# SCH_Aether_Zero_R0_1.net
KiCad netlist of a schematic drawn in EasyEDA
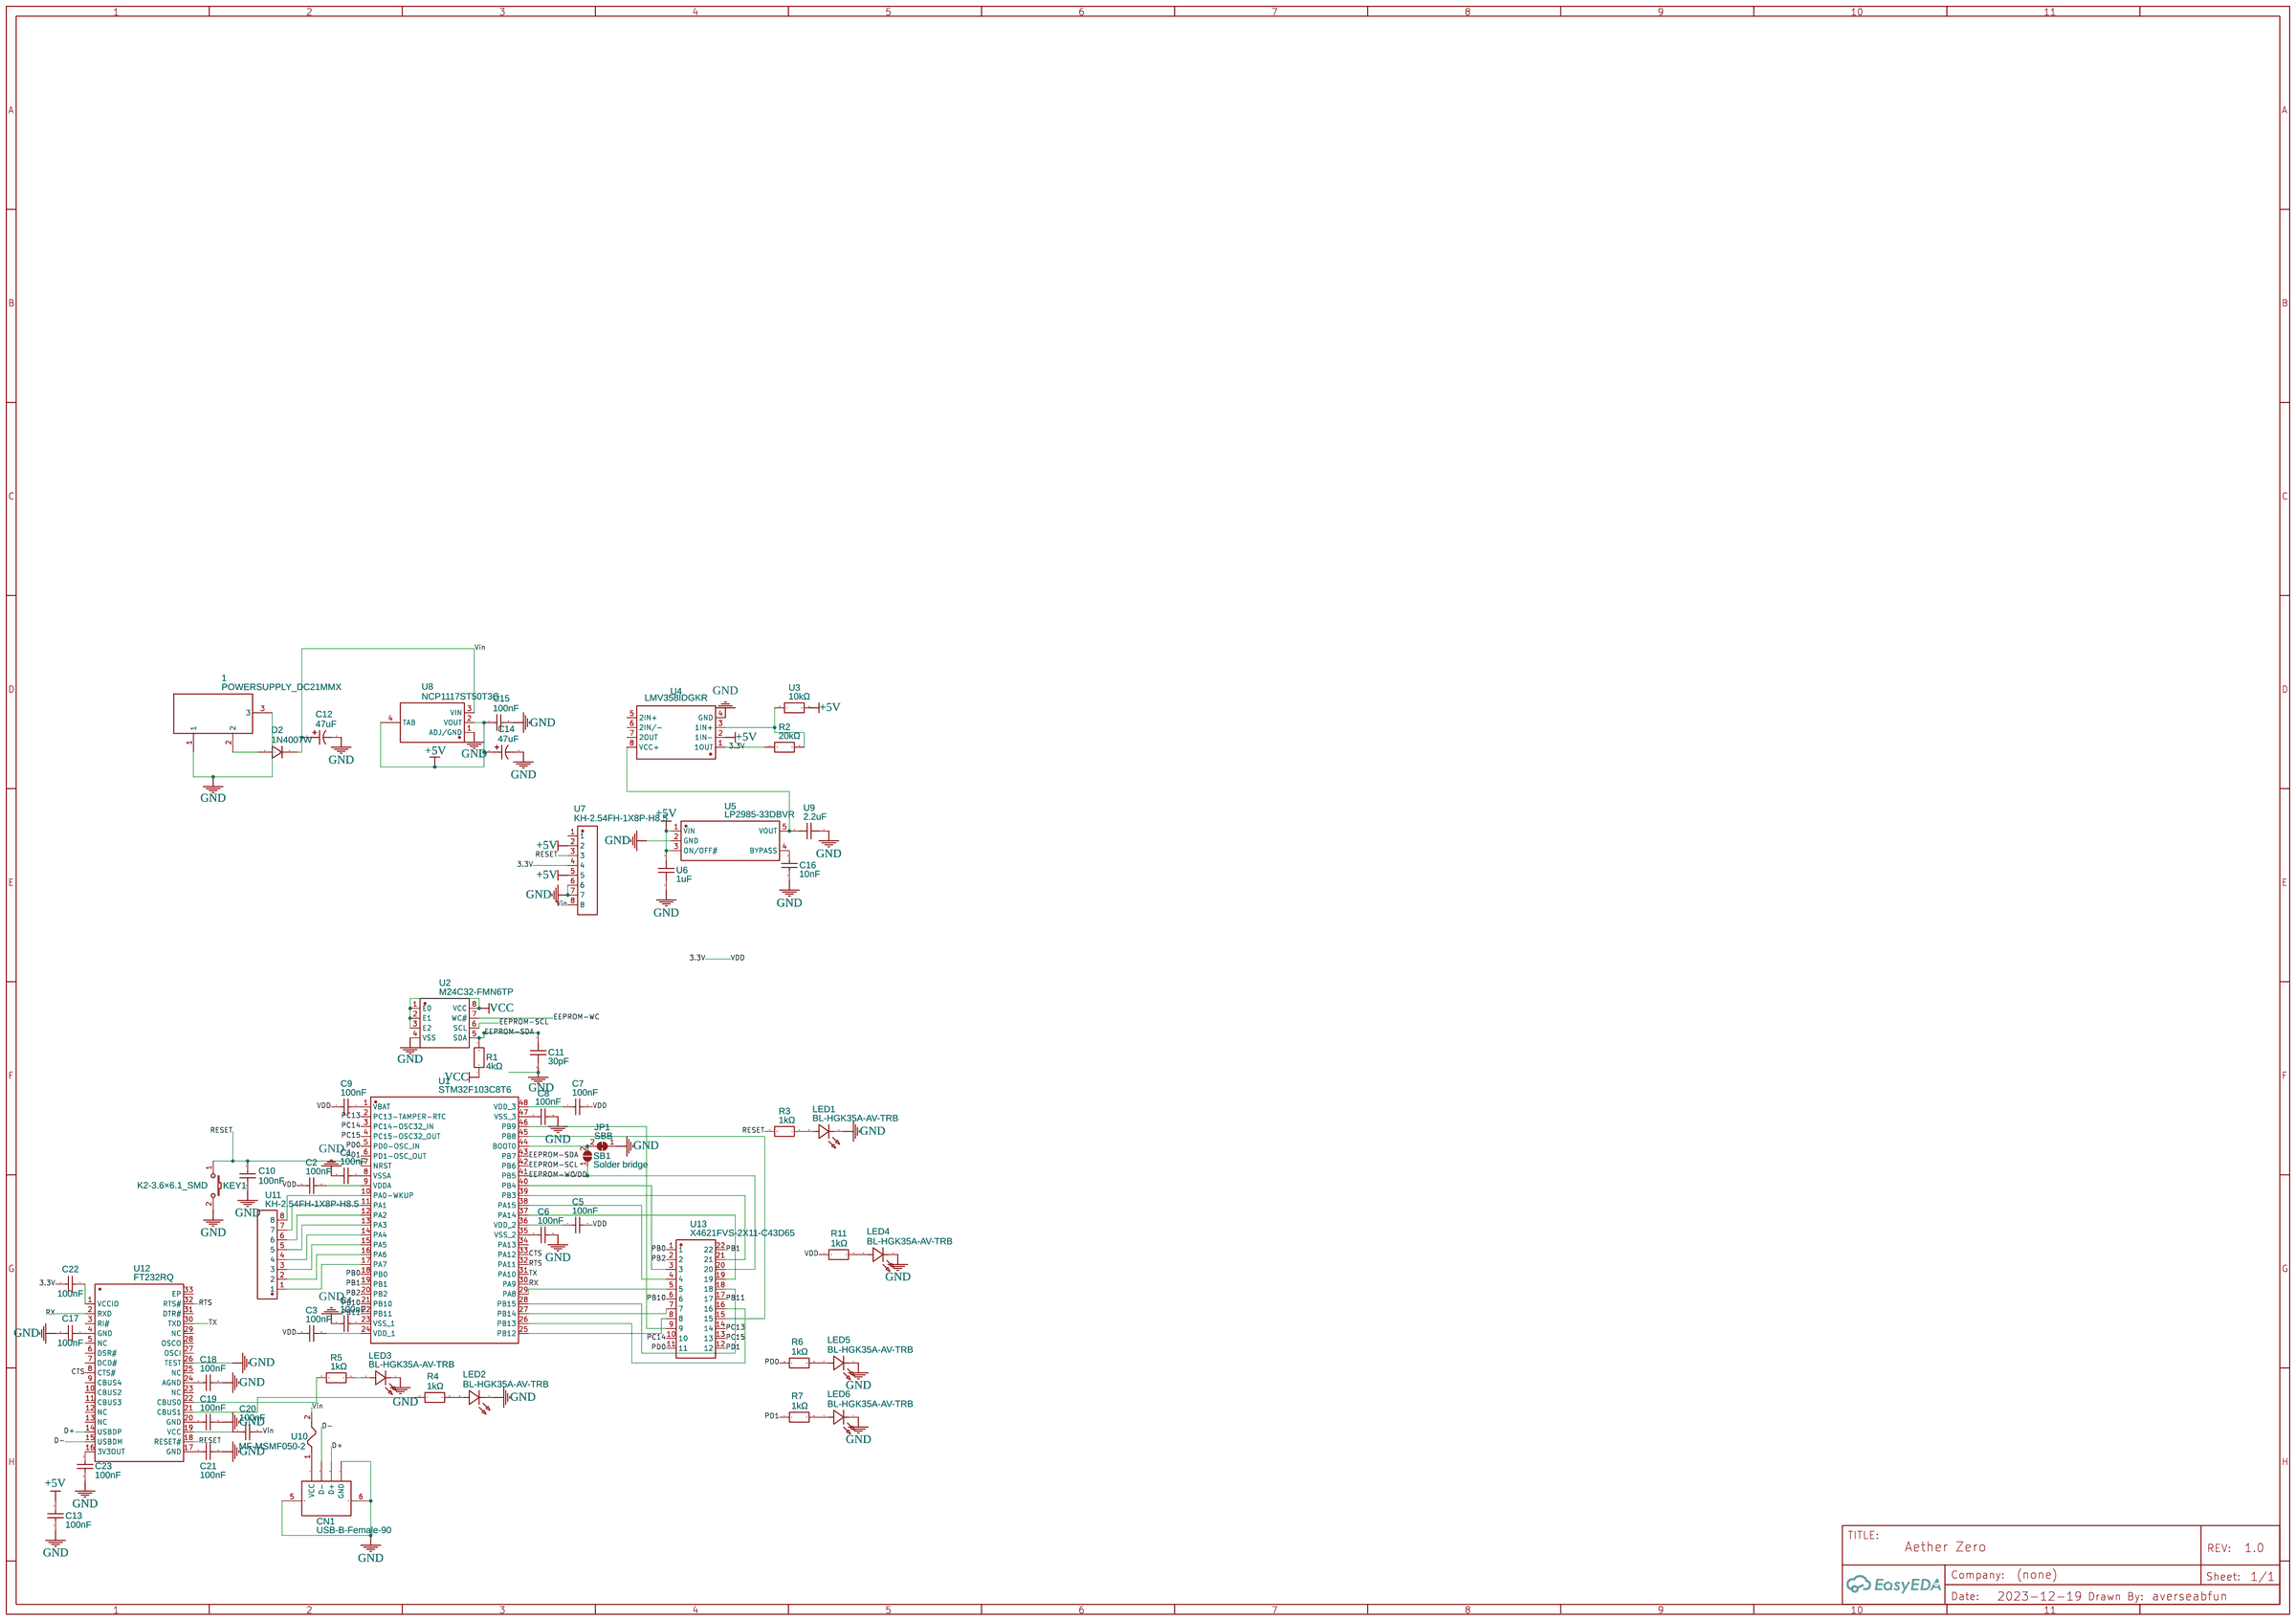
[diagram p0: schematic sheet]

(export (version "E")
  (design (tool "Eeschema 10.0.6"))
  (components
    (comp (ref "1") (value "POWERSUPPLY_DC21MMX") (libsource (lib "") (part "POWERSUPPLY_DC21MMX")))
    (comp (ref "C1")
      (value "100nF")
      (fields (field (name "Manufacturer Part") "0402B104K160NT") (field (name "Manufacturer") "FH(风华)"))
      (libsource (lib "") (part "0402B104K160NT_2"))
    )
    (comp (ref "C2")
      (value "100nF")
      (fields (field (name "Manufacturer Part") "0402B104K160NT") (field (name "Manufacturer") "FH(风华)"))
      (libsource (lib "") (part "0402B104K160NT_2"))
    )
    (comp (ref "C3")
      (value "100nF")
      (fields (field (name "Manufacturer Part") "0402B104K160NT") (field (name "Manufacturer") "FH(风华)"))
      (libsource (lib "") (part "0402B104K160NT_2"))
    )
    (comp (ref "C4")
      (value "100nF")
      (fields (field (name "Manufacturer Part") "0402B104K160NT") (field (name "Manufacturer") "FH(风华)"))
      (libsource (lib "") (part "0402B104K160NT_2"))
    )
    (comp (ref "C5")
      (value "100nF")
      (fields (field (name "Manufacturer Part") "0402B104K160NT") (field (name "Manufacturer") "FH(风华)"))
      (libsource (lib "") (part "0402B104K160NT"))
    )
    (comp (ref "C6")
      (value "100nF")
      (fields (field (name "Manufacturer Part") "0402B104K160NT") (field (name "Manufacturer") "FH(风华)"))
      (libsource (lib "") (part "0402B104K160NT"))
    )
    (comp (ref "C7")
      (value "100nF")
      (fields (field (name "Manufacturer Part") "0402B104K160NT") (field (name "Manufacturer") "FH(风华)"))
      (libsource (lib "") (part "0402B104K160NT"))
    )
    (comp (ref "C8")
      (value "100nF")
      (fields (field (name "Manufacturer Part") "0402B104K160NT") (field (name "Manufacturer") "FH(风华)"))
      (libsource (lib "") (part "0402B104K160NT"))
    )
    (comp (ref "C9")
      (value "100nF")
      (fields (field (name "Manufacturer Part") "0402B104K160NT") (field (name "Manufacturer") "FH(风华)"))
      (libsource (lib "") (part "0402B104K160NT_2"))
    )
    (comp (ref "C10")
      (value "100nF")
      (fields (field (name "Manufacturer Part") "0402B104K160NT") (field (name "Manufacturer") "FH(风华)"))
      (libsource (lib "") (part "0402B104K160NT_1"))
    )
    (comp (ref "C11")
      (value "30pF")
      (fields
        (field (name "Manufacturer Part") "AC0402JRNPO9BN300")
        (field (name "Manufacturer") "YAGEO(国巨)")
      )
      (libsource (lib "") (part "AC0402JRNPO9BN300"))
    )
    (comp (ref "C12")
      (value "47uF")
      (fields
        (field (name "Manufacturer Part") "RVT47UF35V67RV0039")
        (field (name "Manufacturer") "KNSCHA(科尼盛)")
      )
      (libsource (lib "") (part "RVT47UF35V67RV0039"))
    )
    (comp (ref "C13")
      (value "100nF")
      (fields (field (name "Manufacturer Part") "0402B104K160NT") (field (name "Manufacturer") "FH(风华)"))
      (libsource (lib "") (part "0402B104K160NT_3"))
    )
    (comp (ref "C14")
      (value "47uF")
      (fields
        (field (name "Manufacturer Part") "RVT47UF35V67RV0039")
        (field (name "Manufacturer") "KNSCHA(科尼盛)")
      )
      (libsource (lib "") (part "RVT47UF35V67RV0039"))
    )
    (comp (ref "C15")
      (value "100nF")
      (fields (field (name "Manufacturer Part") "0402B104K160NT") (field (name "Manufacturer") "FH(风华)"))
      (libsource (lib "") (part "0402B104K160NT"))
    )
    (comp (ref "C16")
      (value "10nF")
      (fields (field (name "Manufacturer Part") "0402B103K500NT") (field (name "Manufacturer") "FH(风华)"))
      (libsource (lib "") (part "0402B103K500NT"))
    )
    (comp (ref "C17")
      (value "100nF")
      (fields (field (name "Manufacturer Part") "0402B104K160NT") (field (name "Manufacturer") "FH(风华)"))
      (libsource (lib "") (part "0402B104K160NT_2"))
    )
    (comp (ref "C18")
      (value "100nF")
      (fields (field (name "Manufacturer Part") "0402B104K160NT") (field (name "Manufacturer") "FH(风华)"))
      (libsource (lib "") (part "0402B104K160NT"))
    )
    (comp (ref "C19")
      (value "100nF")
      (fields (field (name "Manufacturer Part") "0402B104K160NT") (field (name "Manufacturer") "FH(风华)"))
      (libsource (lib "") (part "0402B104K160NT"))
    )
    (comp (ref "C20")
      (value "100nF")
      (fields (field (name "Manufacturer Part") "0402B104K160NT") (field (name "Manufacturer") "FH(风华)"))
      (libsource (lib "") (part "0402B104K160NT"))
    )
    (comp (ref "C21")
      (value "100nF")
      (fields (field (name "Manufacturer Part") "0402B104K160NT") (field (name "Manufacturer") "FH(风华)"))
      (libsource (lib "") (part "0402B104K160NT"))
    )
    (comp (ref "C22")
      (value "100nF")
      (fields (field (name "Manufacturer Part") "0402B104K160NT") (field (name "Manufacturer") "FH(风华)"))
      (libsource (lib "") (part "0402B104K160NT_2"))
    )
    (comp (ref "C23")
      (value "100nF")
      (fields (field (name "Manufacturer Part") "0402B104K160NT") (field (name "Manufacturer") "FH(风华)"))
      (libsource (lib "") (part "0402B104K160NT_1"))
    )
    (comp (ref "CN1")
      (value "USB-B-Female-90")
      (fields (field (name "Manufacturer Part") "921-111A1010D10200") (field (name "Manufacturer") "精拓金"))
      (libsource (lib "") (part "USB-B-Female-90"))
    )
    (comp (ref "D2")
      (value "1N4007W")
      (fields (field (name "Manufacturer") "BLUE ROCKET"))
      (libsource (lib "") (part "1N4007W"))
    )
    (comp (ref "JP1") (value "SBB") (libsource (lib "") (part "SBB")))
    (comp (ref "KEY1")
      (value "K2-3.6×6.1_SMD")
      (fields (field (name "Manufacturer Part") "K2-1107ST-A4SW-06"))
      (libsource (lib "") (part "K2-3.6×6.1_SMD"))
    )
    (comp (ref "LED1")
      (value "BL-HGK35A-AV-TRB")
      (fields (field (name "Manufacturer") "BrtLed(佰鸿)"))
      (libsource (lib "") (part "BL-HGK35A-AV-TRB"))
    )
    (comp (ref "LED2")
      (value "BL-HGK35A-AV-TRB")
      (fields (field (name "Manufacturer") "BrtLed(佰鸿)"))
      (libsource (lib "") (part "BL-HGK35A-AV-TRB"))
    )
    (comp (ref "LED3")
      (value "BL-HGK35A-AV-TRB")
      (fields (field (name "Manufacturer") "BrtLed(佰鸿)"))
      (libsource (lib "") (part "BL-HGK35A-AV-TRB"))
    )
    (comp (ref "LED4")
      (value "BL-HGK35A-AV-TRB")
      (fields (field (name "Manufacturer") "BrtLed(佰鸿)"))
      (libsource (lib "") (part "BL-HGK35A-AV-TRB"))
    )
    (comp (ref "LED5")
      (value "BL-HGK35A-AV-TRB")
      (fields (field (name "Manufacturer") "BrtLed(佰鸿)"))
      (libsource (lib "") (part "BL-HGK35A-AV-TRB"))
    )
    (comp (ref "LED6")
      (value "BL-HGK35A-AV-TRB")
      (fields (field (name "Manufacturer") "BrtLed(佰鸿)"))
      (libsource (lib "") (part "BL-HGK35A-AV-TRB"))
    )
    (comp (ref "R1")
      (value "4kΩ")
      (fields (field (name "Manufacturer Part") "RN732BTTD4001B25") (field (name "Manufacturer") "KOA"))
      (libsource (lib "") (part "RN732BTTD4001B25"))
    )
    (comp (ref "R2")
      (value "20kΩ")
      (fields (field (name "Manufacturer Part") "RT0402BRD0720KL") (field (name "Manufacturer") "YAGEO(国巨)"))
      (libsource (lib "") (part "RT0402BRD0720KL"))
    )
    (comp (ref "R3")
      (value "1kΩ")
      (fields (field (name "Manufacturer Part") "CR-03JA7----1K") (field (name "Manufacturer") "Viking Tech"))
      (libsource (lib "") (part "CR-03JA7----1K_1"))
    )
    (comp (ref "R4")
      (value "1kΩ")
      (fields (field (name "Manufacturer Part") "CR-03JA7----1K") (field (name "Manufacturer") "Viking Tech"))
      (libsource (lib "") (part "CR-03JA7----1K"))
    )
    (comp (ref "R5")
      (value "1kΩ")
      (fields (field (name "Manufacturer Part") "CR-03JA7----1K") (field (name "Manufacturer") "Viking Tech"))
      (libsource (lib "") (part "CR-03JA7----1K_1"))
    )
    (comp (ref "R6")
      (value "1kΩ")
      (fields (field (name "Manufacturer Part") "CR-03JA7----1K") (field (name "Manufacturer") "Viking Tech"))
      (libsource (lib "") (part "CR-03JA7----1K"))
    )
    (comp (ref "R7")
      (value "1kΩ")
      (fields (field (name "Manufacturer Part") "CR-03JA7----1K") (field (name "Manufacturer") "Viking Tech"))
      (libsource (lib "") (part "CR-03JA7----1K"))
    )
    (comp (ref "R11")
      (value "1kΩ")
      (fields (field (name "Manufacturer Part") "CR-03JA7----1K") (field (name "Manufacturer") "Viking Tech"))
      (libsource (lib "") (part "CR-03JA7----1K"))
    )
    (comp (ref "SB1")
      (value "Solder bridge")
      (fields (field (name "Manufacturer Part") "DNP"))
      (libsource (lib "") (part "Solder bridge"))
    )
    (comp (ref "U1")
      (value "STM32F103C8T6")
      (fields (field (name "Manufacturer") "ST(意法半导体)"))
      (libsource (lib "") (part "STM32F103C8T6"))
    )
    (comp (ref "U2")
      (value "M24C32-FMN6TP")
      (fields (field (name "Manufacturer") "ST(意法半导体)"))
      (libsource (lib "") (part "M24C32-FMN6TP"))
    )
    (comp (ref "U3")
      (value "10kΩ")
      (fields
        (field (name "Manufacturer Part") "TC0625B1002T5J")
        (field (name "Manufacturer") "UNI-ROYAL(厚声)")
      )
      (libsource (lib "") (part "TC0625B1002T5J"))
    )
    (comp (ref "U4")
      (value "LMV358IDGKR")
      (fields (field (name "Manufacturer") "TI(德州仪器)"))
      (libsource (lib "") (part "LMV358IDGKR"))
    )
    (comp (ref "U5")
      (value "LP2985-33DBVR")
      (fields (field (name "Manufacturer") "TI(德州仪器)"))
      (libsource (lib "") (part "LP2985-33DBVR"))
    )
    (comp (ref "U6")
      (value "1uF")
      (fields (field (name "Manufacturer Part") "CGA5L3X8R1H105KT0Y0N") (field (name "Manufacturer") "TDK"))
      (libsource (lib "") (part "CGA5L3X8R1H105KT0Y0N"))
    )
    (comp (ref "U7")
      (value "KH-2.54FH-1X8P-H8.5")
      (fields (field (name "Manufacturer") "kinghelm(金航标)"))
      (libsource (lib "") (part "KH-2.54FH-1X8P-H8.5_1"))
    )
    (comp (ref "U8")
      (value "NCP1117ST50T3G")
      (fields (field (name "Manufacturer") "onsemi(安森美)"))
      (libsource (lib "") (part "NCP1117ST50T3G"))
    )
    (comp (ref "U9")
      (value "2.2uF")
      (fields (field (name "Manufacturer Part") "0805X225K250CT") (field (name "Manufacturer") "Walsin(华新科)"))
      (libsource (lib "") (part "0805X225K250CT_C5122273"))
    )
    (comp (ref "U10")
      (value "MF-MSMF050-2")
      (fields (field (name "Manufacturer") "BOURNS"))
      (libsource (lib "") (part "MF-MSMF050-2"))
    )
    (comp (ref "U11")
      (value "KH-2.54FH-1X8P-H8.5")
      (fields (field (name "Manufacturer") "kinghelm(金航标)"))
      (libsource (lib "") (part "KH-2.54FH-1X8P-H8.5"))
    )
    (comp (ref "U12")
      (value "FT232RQ")
      (fields (field (name "Manufacturer Part") "FT232RQ-REEL") (field (name "Manufacturer") "FTDI(飞特帝亚)"))
      (libsource (lib "") (part "FT232RQ"))
    )
    (comp (ref "U13")
      (value "X4621FVS-2X11-C43D65")
      (fields
        (field (name "Manufacturer Part") "X4621FVS-2x11-C43D65")
        (field (name "Manufacturer") "XKB Connectivity(中国星坤)")
      )
      (libsource (lib "") (part "X4621FVS-2X11-C43D65"))
    )
  )
  (nets
    (net (code "1") (name "+5V") (class "Default")
      (node (ref "C13") (pin "2") (pinfunction "2_2") (pintype "input"))
      (node (ref "C14") (pin "1") (pinfunction "1_1") (pintype "input"))
      (node (ref "C15") (pin "1") (pinfunction "1_1") (pintype "input"))
      (node (ref "U3") (pin "2") (pinfunction "2_2") (pintype "unspecified"))
      (node (ref "U4") (pin "2") (pinfunction "1IN-_2") (pintype "unspecified"))
      (node (ref "U5") (pin "1") (pinfunction "VIN_1") (pintype "unspecified"))
      (node (ref "U5") (pin "3") (pinfunction "ON/OFF#_3") (pintype "unspecified"))
      (node (ref "U6") (pin "2") (pinfunction "2_2") (pintype "unspecified"))
      (node (ref "U7") (pin "2") (pinfunction "2_2") (pintype "unspecified"))
      (node (ref "U7") (pin "5") (pinfunction "5_5") (pintype "unspecified"))
      (node (ref "U8") (pin "2") (pinfunction "VOUT_2") (pintype "unspecified"))
      (node (ref "U8") (pin "4") (pinfunction "TAB_4") (pintype "unspecified"))
    )
    (net (code "2") (name "/3.3V") (class "Default")
      (node (ref "C2") (pin "2") (pinfunction "2_2") (pintype "input"))
      (node (ref "C22") (pin "2") (pinfunction "2_2") (pintype "input"))
      (node (ref "C3") (pin "2") (pinfunction "2_2") (pintype "input"))
      (node (ref "C5") (pin "2") (pinfunction "2_2") (pintype "input"))
      (node (ref "C7") (pin "2") (pinfunction "2_2") (pintype "input"))
      (node (ref "C9") (pin "2") (pinfunction "2_2") (pintype "input"))
      (node (ref "R11") (pin "1") (pinfunction "1_1") (pintype "unspecified"))
      (node (ref "R2") (pin "1") (pinfunction "1_1") (pintype "unspecified"))
      (node (ref "SB1") (pin "1") (pinfunction "A_1") (pintype "unspecified"))
      (node (ref "U1") (pin "41") (pinfunction "PB5_41") (pintype "unspecified"))
      (node (ref "U13") (pin "20") (pinfunction "20_20") (pintype "unspecified"))
      (node (ref "U2") (pin "7") (pinfunction "WC#_7") (pintype "unspecified"))
      (node (ref "U4") (pin "1") (pinfunction "1OUT_1") (pintype "unspecified"))
      (node (ref "U7") (pin "4") (pinfunction "4_4") (pintype "unspecified"))
    )
    (net (code "3") (name "/CTS") (class "Default")
      (node (ref "U1") (pin "33") (pinfunction "PA12_33") (pintype "unspecified"))
      (node (ref "U12") (pin "8") (pinfunction "CTS#_8") (pintype "unspecified"))
    )
    (net (code "4") (name "/D+") (class "Default")
      (node (ref "CN1") (pin "3") (pinfunction "D+_3") (pintype "input"))
      (node (ref "U12") (pin "14") (pinfunction "USBDP_14") (pintype "unspecified"))
    )
    (net (code "5") (name "/D-") (class "Default")
      (node (ref "CN1") (pin "2") (pinfunction "D-_2") (pintype "input"))
      (node (ref "U12") (pin "15") (pinfunction "USBDM_15") (pintype "unspecified"))
    )
    (net (code "6") (name "/EEPROM-SCL") (class "Default")
      (node (ref "U1") (pin "42") (pinfunction "PB6_42") (pintype "unspecified"))
      (node (ref "U2") (pin "6") (pinfunction "SCL_6") (pintype "unspecified"))
    )
    (net (code "7") (name "/EEPROM-SDA") (class "Default")
      (node (ref "C11") (pin "1") (pinfunction "1_1") (pintype "unspecified"))
      (node (ref "R1") (pin "2") (pinfunction "2_2") (pintype "unspecified"))
      (node (ref "U1") (pin "43") (pinfunction "PB7_43") (pintype "unspecified"))
      (node (ref "U2") (pin "5") (pinfunction "SDA_5") (pintype "unspecified"))
    )
    (net (code "8") (name "/PB0") (class "Default")
      (node (ref "U1") (pin "18") (pinfunction "PB0_18") (pintype "unspecified"))
      (node (ref "U13") (pin "1") (pinfunction "1_1") (pintype "unspecified"))
    )
    (net (code "9") (name "/PB1") (class "Default")
      (node (ref "U1") (pin "19") (pinfunction "PB1_19") (pintype "unspecified"))
      (node (ref "U13") (pin "22") (pinfunction "22_22") (pintype "unspecified"))
    )
    (net (code "10") (name "/PB2") (class "Default")
      (node (ref "U1") (pin "20") (pinfunction "PB2_20") (pintype "unspecified"))
      (node (ref "U13") (pin "2") (pinfunction "2_2") (pintype "unspecified"))
    )
    (net (code "11") (name "/PB10") (class "Default")
      (node (ref "U1") (pin "21") (pinfunction "PB10_21") (pintype "unspecified"))
      (node (ref "U13") (pin "6") (pinfunction "6_6") (pintype "unspecified"))
    )
    (net (code "12") (name "/PB11") (class "Default")
      (node (ref "U1") (pin "22") (pinfunction "PB11_22") (pintype "unspecified"))
      (node (ref "U13") (pin "17") (pinfunction "17_17") (pintype "unspecified"))
    )
    (net (code "13") (name "/PC13") (class "Default")
      (node (ref "U1") (pin "2") (pinfunction "PC13-TAMPER-RTC_2") (pintype "unspecified"))
      (node (ref "U13") (pin "14") (pinfunction "14_14") (pintype "unspecified"))
    )
    (net (code "14") (name "/PC14") (class "Default")
      (node (ref "U1") (pin "3") (pinfunction "PC14-OSC32_IN_3") (pintype "unspecified"))
      (node (ref "U13") (pin "10") (pinfunction "10_10") (pintype "unspecified"))
    )
    (net (code "15") (name "/PC15") (class "Default")
      (node (ref "U1") (pin "4") (pinfunction "PC15-OSC32_OUT_4") (pintype "unspecified"))
      (node (ref "U13") (pin "13") (pinfunction "13_13") (pintype "unspecified"))
    )
    (net (code "16") (name "/PD0") (class "Default")
      (node (ref "R6") (pin "1") (pinfunction "1_1") (pintype "unspecified"))
      (node (ref "U1") (pin "5") (pinfunction "PD0-OSC_IN_5") (pintype "unspecified"))
      (node (ref "U13") (pin "11") (pinfunction "11_11") (pintype "unspecified"))
    )
    (net (code "17") (name "/PD1") (class "Default")
      (node (ref "R7") (pin "1") (pinfunction "1_1") (pintype "unspecified"))
      (node (ref "U1") (pin "6") (pinfunction "PD1-OSC_OUT_6") (pintype "unspecified"))
      (node (ref "U13") (pin "12") (pinfunction "12_12") (pintype "unspecified"))
    )
    (net (code "18") (name "/RESET") (class "Default")
      (node (ref "C10") (pin "1") (pinfunction "1_1") (pintype "input"))
      (node (ref "KEY1") (pin "1") (pinfunction "1_1") (pintype "unspecified"))
      (node (ref "R3") (pin "2") (pinfunction "2_2") (pintype "unspecified"))
      (node (ref "U1") (pin "7") (pinfunction "NRST_7") (pintype "unspecified"))
      (node (ref "U12") (pin "18") (pinfunction "RESET#_18") (pintype "unspecified"))
      (node (ref "U7") (pin "3") (pinfunction "3_3") (pintype "unspecified"))
    )
    (net (code "19") (name "/RTS") (class "Default")
      (node (ref "U1") (pin "32") (pinfunction "PA11_32") (pintype "unspecified"))
      (node (ref "U12") (pin "32") (pinfunction "RTS#_32") (pintype "unspecified"))
    )
    (net (code "20") (name "/RX") (class "Default")
      (node (ref "U1") (pin "30") (pinfunction "PA9_30") (pintype "unspecified"))
      (node (ref "U12") (pin "2") (pinfunction "RXD_2") (pintype "unspecified"))
    )
    (net (code "21") (name "/TX") (class "Default")
      (node (ref "U1") (pin "31") (pinfunction "PA10_31") (pintype "unspecified"))
      (node (ref "U12") (pin "30") (pinfunction "TXD_30") (pintype "unspecified"))
    )
    (net (code "22") (name "/Vin") (class "Default")
      (node (ref "C12") (pin "1") (pinfunction "1_1") (pintype "input"))
      (node (ref "C20") (pin "2") (pinfunction "2_2") (pintype "input"))
      (node (ref "D2") (pin "1") (pinfunction "1_1") (pintype "unspecified"))
      (node (ref "U10") (pin "2") (pinfunction "2_2") (pintype "unspecified"))
      (node (ref "U7") (pin "8") (pinfunction "8_8") (pintype "unspecified"))
      (node (ref "U8") (pin "3") (pinfunction "VIN_3") (pintype "unspecified"))
    )
    (net (code "23") (name "GND") (class "Default")
      (node (ref "1") (pin "1") (pinfunction "1_1") (pintype "bidirectional"))
      (node (ref "1") (pin "3") (pinfunction "3_3") (pintype "bidirectional"))
      (node (ref "C1") (pin "2") (pinfunction "2_2") (pintype "input"))
      (node (ref "C10") (pin "2") (pinfunction "2_2") (pintype "input"))
      (node (ref "C11") (pin "2") (pinfunction "2_2") (pintype "unspecified"))
      (node (ref "C12") (pin "2") (pinfunction "2_2") (pintype "input"))
      (node (ref "C13") (pin "1") (pinfunction "1_1") (pintype "input"))
      (node (ref "C14") (pin "2") (pinfunction "2_2") (pintype "input"))
      (node (ref "C15") (pin "2") (pinfunction "2_2") (pintype "input"))
      (node (ref "C16") (pin "1") (pinfunction "1_1") (pintype "input"))
      (node (ref "C17") (pin "2") (pinfunction "2_2") (pintype "input"))
      (node (ref "C18") (pin "2") (pinfunction "2_2") (pintype "input"))
      (node (ref "C19") (pin "2") (pinfunction "2_2") (pintype "input"))
      (node (ref "C21") (pin "2") (pinfunction "2_2") (pintype "input"))
      (node (ref "C23") (pin "2") (pinfunction "2_2") (pintype "input"))
      (node (ref "C4") (pin "2") (pinfunction "2_2") (pintype "input"))
      (node (ref "C6") (pin "2") (pinfunction "2_2") (pintype "input"))
      (node (ref "C8") (pin "2") (pinfunction "2_2") (pintype "input"))
      (node (ref "CN1") (pin "4") (pinfunction "GND_4") (pintype "input"))
      (node (ref "CN1") (pin "5") (pinfunction "SH1_5") (pintype "unspecified"))
      (node (ref "CN1") (pin "6") (pinfunction "SH2_6") (pintype "unspecified"))
      (node (ref "JP1") (pin "1") (pinfunction "A_1") (pintype "unspecified"))
      (node (ref "KEY1") (pin "2") (pinfunction "2_2") (pintype "unspecified"))
      (node (ref "LED1") (pin "1") (pinfunction "K_1") (pintype "unspecified"))
      (node (ref "LED2") (pin "1") (pinfunction "K_1") (pintype "unspecified"))
      (node (ref "LED3") (pin "1") (pinfunction "K_1") (pintype "unspecified"))
      (node (ref "LED4") (pin "1") (pinfunction "K_1") (pintype "unspecified"))
      (node (ref "LED5") (pin "1") (pinfunction "K_1") (pintype "unspecified"))
      (node (ref "LED6") (pin "1") (pinfunction "K_1") (pintype "unspecified"))
      (node (ref "U12") (pin "26") (pinfunction "TEST_26") (pintype "unspecified"))
      (node (ref "U2") (pin "4") (pinfunction "VSS_4") (pintype "unspecified"))
      (node (ref "U4") (pin "4") (pinfunction "GND_4") (pintype "unspecified"))
      (node (ref "U5") (pin "2") (pinfunction "GND_2") (pintype "unspecified"))
      (node (ref "U6") (pin "1") (pinfunction "1_1") (pintype "unspecified"))
      (node (ref "U7") (pin "6") (pinfunction "6_6") (pintype "unspecified"))
      (node (ref "U7") (pin "7") (pinfunction "7_7") (pintype "unspecified"))
      (node (ref "U8") (pin "1") (pinfunction "ADJ/GND_1") (pintype "unspecified"))
      (node (ref "U9") (pin "1") (pinfunction "1_1") (pintype "unspecified"))
    )
    (net (code "24") (name "Net-(1-Pad2)") (class "Default")
      (node (ref "1") (pin "2") (pinfunction "2_2") (pintype "bidirectional"))
      (node (ref "D2") (pin "2") (pinfunction "2_2") (pintype "unspecified"))
    )
    (net (code "25") (name "Net-(C17-Pad1)") (class "Default")
      (node (ref "C17") (pin "1") (pinfunction "1_1") (pintype "input"))
      (node (ref "U12") (pin "4") (pinfunction "GND_4") (pintype "unspecified"))
    )
    (net (code "26") (name "Net-(C19-Pad1)") (class "Default")
      (node (ref "C19") (pin "1") (pinfunction "1_1") (pintype "input"))
      (node (ref "U12") (pin "20") (pinfunction "GND_20") (pintype "unspecified"))
    )
    (net (code "27") (name "Net-(C21-Pad1)") (class "Default")
      (node (ref "C21") (pin "1") (pinfunction "1_1") (pintype "input"))
      (node (ref "U12") (pin "17") (pinfunction "GND_17") (pintype "unspecified"))
    )
    (net (code "28") (name "Net-(CN1-VCC)") (class "Default")
      (node (ref "CN1") (pin "1") (pinfunction "VCC_1") (pintype "input"))
      (node (ref "U10") (pin "1") (pinfunction "1_1") (pintype "unspecified"))
    )
    (net (code "29") (name "Net-(JP1-B)") (class "Default")
      (node (ref "JP1") (pin "2") (pinfunction "B_2") (pintype "unspecified"))
      (node (ref "SB1") (pin "2") (pinfunction "B_2") (pintype "unspecified"))
      (node (ref "U1") (pin "44") (pinfunction "BOOT0_44") (pintype "unspecified"))
    )
    (net (code "30") (name "Net-(LED1-A)") (class "Default")
      (node (ref "LED1") (pin "2") (pinfunction "A_2") (pintype "unspecified"))
      (node (ref "R3") (pin "1") (pinfunction "1_1") (pintype "unspecified"))
    )
    (net (code "31") (name "Net-(LED2-A)") (class "Default")
      (node (ref "LED2") (pin "2") (pinfunction "A_2") (pintype "unspecified"))
      (node (ref "R4") (pin "2") (pinfunction "2_2") (pintype "unspecified"))
    )
    (net (code "32") (name "Net-(LED3-A)") (class "Default")
      (node (ref "LED3") (pin "2") (pinfunction "A_2") (pintype "unspecified"))
      (node (ref "R5") (pin "1") (pinfunction "1_1") (pintype "unspecified"))
    )
    (net (code "33") (name "Net-(LED4-A)") (class "Default")
      (node (ref "LED4") (pin "2") (pinfunction "A_2") (pintype "unspecified"))
      (node (ref "R11") (pin "2") (pinfunction "2_2") (pintype "unspecified"))
    )
    (net (code "34") (name "Net-(LED5-A)") (class "Default")
      (node (ref "LED5") (pin "2") (pinfunction "A_2") (pintype "unspecified"))
      (node (ref "R6") (pin "2") (pinfunction "2_2") (pintype "unspecified"))
    )
    (net (code "35") (name "Net-(LED6-A)") (class "Default")
      (node (ref "LED6") (pin "2") (pinfunction "A_2") (pintype "unspecified"))
      (node (ref "R7") (pin "2") (pinfunction "2_2") (pintype "unspecified"))
    )
    (net (code "36") (name "Net-(U1-PA0-WKUP)") (class "Default")
      (node (ref "U1") (pin "10") (pinfunction "PA0-WKUP_10") (pintype "unspecified"))
      (node (ref "U11") (pin "8") (pinfunction "8_8") (pintype "unspecified"))
    )
    (net (code "37") (name "Net-(U1-PA1)") (class "Default")
      (node (ref "U1") (pin "11") (pinfunction "PA1_11") (pintype "unspecified"))
      (node (ref "U11") (pin "7") (pinfunction "7_7") (pintype "unspecified"))
    )
    (net (code "38") (name "Net-(U1-PA2)") (class "Default")
      (node (ref "U1") (pin "12") (pinfunction "PA2_12") (pintype "unspecified"))
      (node (ref "U11") (pin "6") (pinfunction "6_6") (pintype "unspecified"))
    )
    (net (code "39") (name "Net-(U1-PA3)") (class "Default")
      (node (ref "U1") (pin "13") (pinfunction "PA3_13") (pintype "unspecified"))
      (node (ref "U11") (pin "5") (pinfunction "5_5") (pintype "unspecified"))
    )
    (net (code "40") (name "Net-(U1-PA4)") (class "Default")
      (node (ref "U1") (pin "14") (pinfunction "PA4_14") (pintype "unspecified"))
      (node (ref "U11") (pin "4") (pinfunction "4_4") (pintype "unspecified"))
    )
    (net (code "41") (name "Net-(U1-PA5)") (class "Default")
      (node (ref "U1") (pin "15") (pinfunction "PA5_15") (pintype "unspecified"))
      (node (ref "U11") (pin "3") (pinfunction "3_3") (pintype "unspecified"))
    )
    (net (code "42") (name "Net-(U1-PA6)") (class "Default")
      (node (ref "U1") (pin "16") (pinfunction "PA6_16") (pintype "unspecified"))
      (node (ref "U11") (pin "2") (pinfunction "2_2") (pintype "unspecified"))
    )
    (net (code "43") (name "Net-(U1-PA7)") (class "Default")
      (node (ref "U1") (pin "17") (pinfunction "PA7_17") (pintype "unspecified"))
      (node (ref "U11") (pin "1") (pinfunction "1_1") (pintype "unspecified"))
    )
    (net (code "44") (name "Net-(U1-PA8)") (class "Default")
      (node (ref "U1") (pin "29") (pinfunction "PA8_29") (pintype "unspecified"))
      (node (ref "U13") (pin "5") (pinfunction "5_5") (pintype "unspecified"))
    )
    (net (code "45") (name "Net-(U1-PA14)") (class "Default")
      (node (ref "U1") (pin "37") (pinfunction "PA14_37") (pintype "unspecified"))
      (node (ref "U13") (pin "19") (pinfunction "19_19") (pintype "unspecified"))
    )
    (net (code "46") (name "Net-(U1-PA15)") (class "Default")
      (node (ref "U1") (pin "38") (pinfunction "PA15_38") (pintype "unspecified"))
      (node (ref "U13") (pin "4") (pinfunction "4_4") (pintype "unspecified"))
    )
    (net (code "47") (name "Net-(U1-PB3)") (class "Default")
      (node (ref "U1") (pin "39") (pinfunction "PB3_39") (pintype "unspecified"))
      (node (ref "U13") (pin "21") (pinfunction "21_21") (pintype "unspecified"))
    )
    (net (code "48") (name "Net-(U1-PB4)") (class "Default")
      (node (ref "U1") (pin "40") (pinfunction "PB4_40") (pintype "unspecified"))
      (node (ref "U13") (pin "3") (pinfunction "3_3") (pintype "unspecified"))
    )
    (net (code "49") (name "Net-(U1-PB8)") (class "Default")
      (node (ref "U1") (pin "45") (pinfunction "PB8_45") (pintype "unspecified"))
      (node (ref "U13") (pin "15") (pinfunction "15_15") (pintype "unspecified"))
    )
    (net (code "50") (name "Net-(U1-PB9)") (class "Default")
      (node (ref "U1") (pin "46") (pinfunction "PB9_46") (pintype "unspecified"))
      (node (ref "U13") (pin "9") (pinfunction "9_9") (pintype "unspecified"))
    )
    (net (code "51") (name "Net-(U1-PB12)") (class "Default")
      (node (ref "U1") (pin "25") (pinfunction "PB12_25") (pintype "unspecified"))
      (node (ref "U13") (pin "8") (pinfunction "8_8") (pintype "unspecified"))
    )
    (net (code "52") (name "Net-(U1-PB13)") (class "Default")
      (node (ref "U1") (pin "26") (pinfunction "PB13_26") (pintype "unspecified"))
      (node (ref "U13") (pin "16") (pinfunction "16_16") (pintype "unspecified"))
    )
    (net (code "53") (name "Net-(U1-PB14)") (class "Default")
      (node (ref "U1") (pin "27") (pinfunction "PB14_27") (pintype "unspecified"))
      (node (ref "U13") (pin "7") (pinfunction "7_7") (pintype "unspecified"))
    )
    (net (code "54") (name "Net-(U1-PB15)") (class "Default")
      (node (ref "U1") (pin "28") (pinfunction "PB15_28") (pintype "unspecified"))
      (node (ref "U13") (pin "18") (pinfunction "18_18") (pintype "unspecified"))
    )
    (net (code "55") (name "Net-(U1-VBAT)") (class "Default")
      (node (ref "C9") (pin "1") (pinfunction "1_1") (pintype "input"))
      (node (ref "U1") (pin "1") (pinfunction "VBAT_1") (pintype "unspecified"))
    )
    (net (code "56") (name "Net-(U1-VDDA)") (class "Default")
      (node (ref "C2") (pin "1") (pinfunction "1_1") (pintype "input"))
      (node (ref "U1") (pin "9") (pinfunction "VDDA_9") (pintype "unspecified"))
    )
    (net (code "57") (name "Net-(U1-VDD_1)") (class "Default")
      (node (ref "C3") (pin "1") (pinfunction "1_1") (pintype "input"))
      (node (ref "U1") (pin "24") (pinfunction "VDD_1_24") (pintype "unspecified"))
    )
    (net (code "58") (name "Net-(U1-VDD_2)") (class "Default")
      (node (ref "C5") (pin "1") (pinfunction "1_1") (pintype "input"))
      (node (ref "U1") (pin "36") (pinfunction "VDD_2_36") (pintype "unspecified"))
    )
    (net (code "59") (name "Net-(U1-VDD_3)") (class "Default")
      (node (ref "C7") (pin "1") (pinfunction "1_1") (pintype "input"))
      (node (ref "U1") (pin "48") (pinfunction "VDD_3_48") (pintype "unspecified"))
    )
    (net (code "60") (name "Net-(U1-VSSA)") (class "Default")
      (node (ref "C1") (pin "1") (pinfunction "1_1") (pintype "input"))
      (node (ref "U1") (pin "8") (pinfunction "VSSA_8") (pintype "unspecified"))
    )
    (net (code "61") (name "Net-(U1-VSS_1)") (class "Default")
      (node (ref "C4") (pin "1") (pinfunction "1_1") (pintype "input"))
      (node (ref "U1") (pin "23") (pinfunction "VSS_1_23") (pintype "unspecified"))
    )
    (net (code "62") (name "Net-(U1-VSS_2)") (class "Default")
      (node (ref "C6") (pin "1") (pinfunction "1_1") (pintype "input"))
      (node (ref "U1") (pin "35") (pinfunction "VSS_2_35") (pintype "unspecified"))
    )
    (net (code "63") (name "Net-(U1-VSS_3)") (class "Default")
      (node (ref "C8") (pin "1") (pinfunction "1_1") (pintype "input"))
      (node (ref "U1") (pin "47") (pinfunction "VSS_3_47") (pintype "unspecified"))
    )
    (net (code "64") (name "Net-(U4-1IN+)") (class "Default")
      (node (ref "R2") (pin "2") (pinfunction "2_2") (pintype "unspecified"))
      (node (ref "U3") (pin "1") (pinfunction "1_1") (pintype "unspecified"))
      (node (ref "U4") (pin "3") (pinfunction "1IN+_3") (pintype "unspecified"))
    )
    (net (code "65") (name "Net-(U4-VCC+)") (class "Default")
      (node (ref "U4") (pin "8") (pinfunction "VCC+_8") (pintype "unspecified"))
      (node (ref "U5") (pin "5") (pinfunction "VOUT_5") (pintype "unspecified"))
      (node (ref "U9") (pin "2") (pinfunction "2_2") (pintype "unspecified"))
    )
    (net (code "66") (name "Net-(U5-BYPASS)") (class "Default")
      (node (ref "C16") (pin "2") (pinfunction "2_2") (pintype "input"))
      (node (ref "U5") (pin "4") (pinfunction "BYPASS_4") (pintype "unspecified"))
    )
    (net (code "67") (name "Net-(U12-3V3OUT)") (class "Default")
      (node (ref "C23") (pin "1") (pinfunction "1_1") (pintype "input"))
      (node (ref "U12") (pin "16") (pinfunction "3V3OUT_16") (pintype "unspecified"))
    )
    (net (code "68") (name "Net-(U12-AGND)") (class "Default")
      (node (ref "C18") (pin "1") (pinfunction "1_1") (pintype "input"))
      (node (ref "U12") (pin "24") (pinfunction "AGND_24") (pintype "unspecified"))
    )
    (net (code "69") (name "Net-(U12-CBUS0)") (class "Default")
      (node (ref "R5") (pin "2") (pinfunction "2_2") (pintype "unspecified"))
      (node (ref "U12") (pin "22") (pinfunction "CBUS0_22") (pintype "unspecified"))
    )
    (net (code "70") (name "Net-(U12-CBUS1)") (class "Default")
      (node (ref "R4") (pin "1") (pinfunction "1_1") (pintype "unspecified"))
      (node (ref "U12") (pin "21") (pinfunction "CBUS1_21") (pintype "unspecified"))
    )
    (net (code "71") (name "Net-(U12-VCC)") (class "Default")
      (node (ref "C20") (pin "1") (pinfunction "1_1") (pintype "input"))
      (node (ref "U12") (pin "19") (pinfunction "VCC_19") (pintype "unspecified"))
    )
    (net (code "72") (name "Net-(U12-VCCIO)") (class "Default")
      (node (ref "C22") (pin "1") (pinfunction "1_1") (pintype "input"))
      (node (ref "U12") (pin "1") (pinfunction "VCCIO_1") (pintype "unspecified"))
    )
    (net (code "73") (name "VCC") (class "Default")
      (node (ref "R1") (pin "1") (pinfunction "1_1") (pintype "unspecified"))
      (node (ref "U2") (pin "1") (pinfunction "E0_1") (pintype "unspecified"))
      (node (ref "U2") (pin "2") (pinfunction "E1_2") (pintype "unspecified"))
      (node (ref "U2") (pin "3") (pinfunction "E2_3") (pintype "unspecified"))
      (node (ref "U2") (pin "8") (pinfunction "VCC_8") (pintype "unspecified"))
    )
    (net (code "74") (name "unconnected-(U1-PA13-Pad34)") (class "Default")
      (node (ref "U1") (pin "34") (pinfunction "PA13_34") (pintype "unspecified"))
    )
    (net (code "75") (name "unconnected-(U4-2IN+-Pad5)") (class "Default")
      (node (ref "U4") (pin "5") (pinfunction "2IN+_5") (pintype "unspecified"))
    )
    (net (code "76") (name "unconnected-(U4-2IN{slash}--Pad6)") (class "Default")
      (node (ref "U4") (pin "6") (pinfunction "2IN/-_6") (pintype "unspecified"))
    )
    (net (code "77") (name "unconnected-(U4-2OUT-Pad7)") (class "Default")
      (node (ref "U4") (pin "7") (pinfunction "2OUT_7") (pintype "unspecified"))
    )
    (net (code "78") (name "unconnected-(U7-Pad1)") (class "Default")
      (node (ref "U7") (pin "1") (pinfunction "1_1") (pintype "unspecified"))
    )
    (net (code "79") (name "unconnected-(U12-CBUS2-Pad10)") (class "Default")
      (node (ref "U12") (pin "10") (pinfunction "CBUS2_10") (pintype "unspecified"))
    )
    (net (code "80") (name "unconnected-(U12-CBUS3-Pad11)") (class "Default")
      (node (ref "U12") (pin "11") (pinfunction "CBUS3_11") (pintype "unspecified"))
    )
    (net (code "81") (name "unconnected-(U12-CBUS4-Pad9)") (class "Default")
      (node (ref "U12") (pin "9") (pinfunction "CBUS4_9") (pintype "unspecified"))
    )
    (net (code "82") (name "unconnected-(U12-DCD#-Pad7)") (class "Default")
      (node (ref "U12") (pin "7") (pinfunction "DCD#_7") (pintype "unspecified"))
    )
    (net (code "83") (name "unconnected-(U12-DSR#-Pad6)") (class "Default")
      (node (ref "U12") (pin "6") (pinfunction "DSR#_6") (pintype "unspecified"))
    )
    (net (code "84") (name "unconnected-(U12-DTR#-Pad31)") (class "Default")
      (node (ref "U12") (pin "31") (pinfunction "DTR#_31") (pintype "unspecified"))
    )
    (net (code "85") (name "unconnected-(U12-EP-Pad33)") (class "Default")
      (node (ref "U12") (pin "33") (pinfunction "EP_33") (pintype "unspecified"))
    )
    (net (code "86") (name "unconnected-(U12-NC-Pad5)") (class "Default")
      (node (ref "U12") (pin "5") (pinfunction "NC_5") (pintype "unspecified"))
    )
    (net (code "87") (name "unconnected-(U12-NC-Pad12)") (class "Default")
      (node (ref "U12") (pin "12") (pinfunction "NC_12") (pintype "unspecified"))
    )
    (net (code "88") (name "unconnected-(U12-NC-Pad13)") (class "Default")
      (node (ref "U12") (pin "13") (pinfunction "NC_13") (pintype "unspecified"))
    )
    (net (code "89") (name "unconnected-(U12-NC-Pad23)") (class "Default")
      (node (ref "U12") (pin "23") (pinfunction "NC_23") (pintype "unspecified"))
    )
    (net (code "90") (name "unconnected-(U12-NC-Pad25)") (class "Default")
      (node (ref "U12") (pin "25") (pinfunction "NC_25") (pintype "unspecified"))
    )
    (net (code "91") (name "unconnected-(U12-NC-Pad29)") (class "Default")
      (node (ref "U12") (pin "29") (pinfunction "NC_29") (pintype "unspecified"))
    )
    (net (code "92") (name "unconnected-(U12-OSCI-Pad27)") (class "Default")
      (node (ref "U12") (pin "27") (pinfunction "OSCI_27") (pintype "unspecified"))
    )
    (net (code "93") (name "unconnected-(U12-OSCO-Pad28)") (class "Default")
      (node (ref "U12") (pin "28") (pinfunction "OSCO_28") (pintype "unspecified"))
    )
    (net (code "94") (name "unconnected-(U12-RI#-Pad3)") (class "Default")
      (node (ref "U12") (pin "3") (pinfunction "RI#_3") (pintype "unspecified"))
    )
  )
)
